# Thermometer1_1.net
KiCad netlist of a schematic drawn in EAGLE
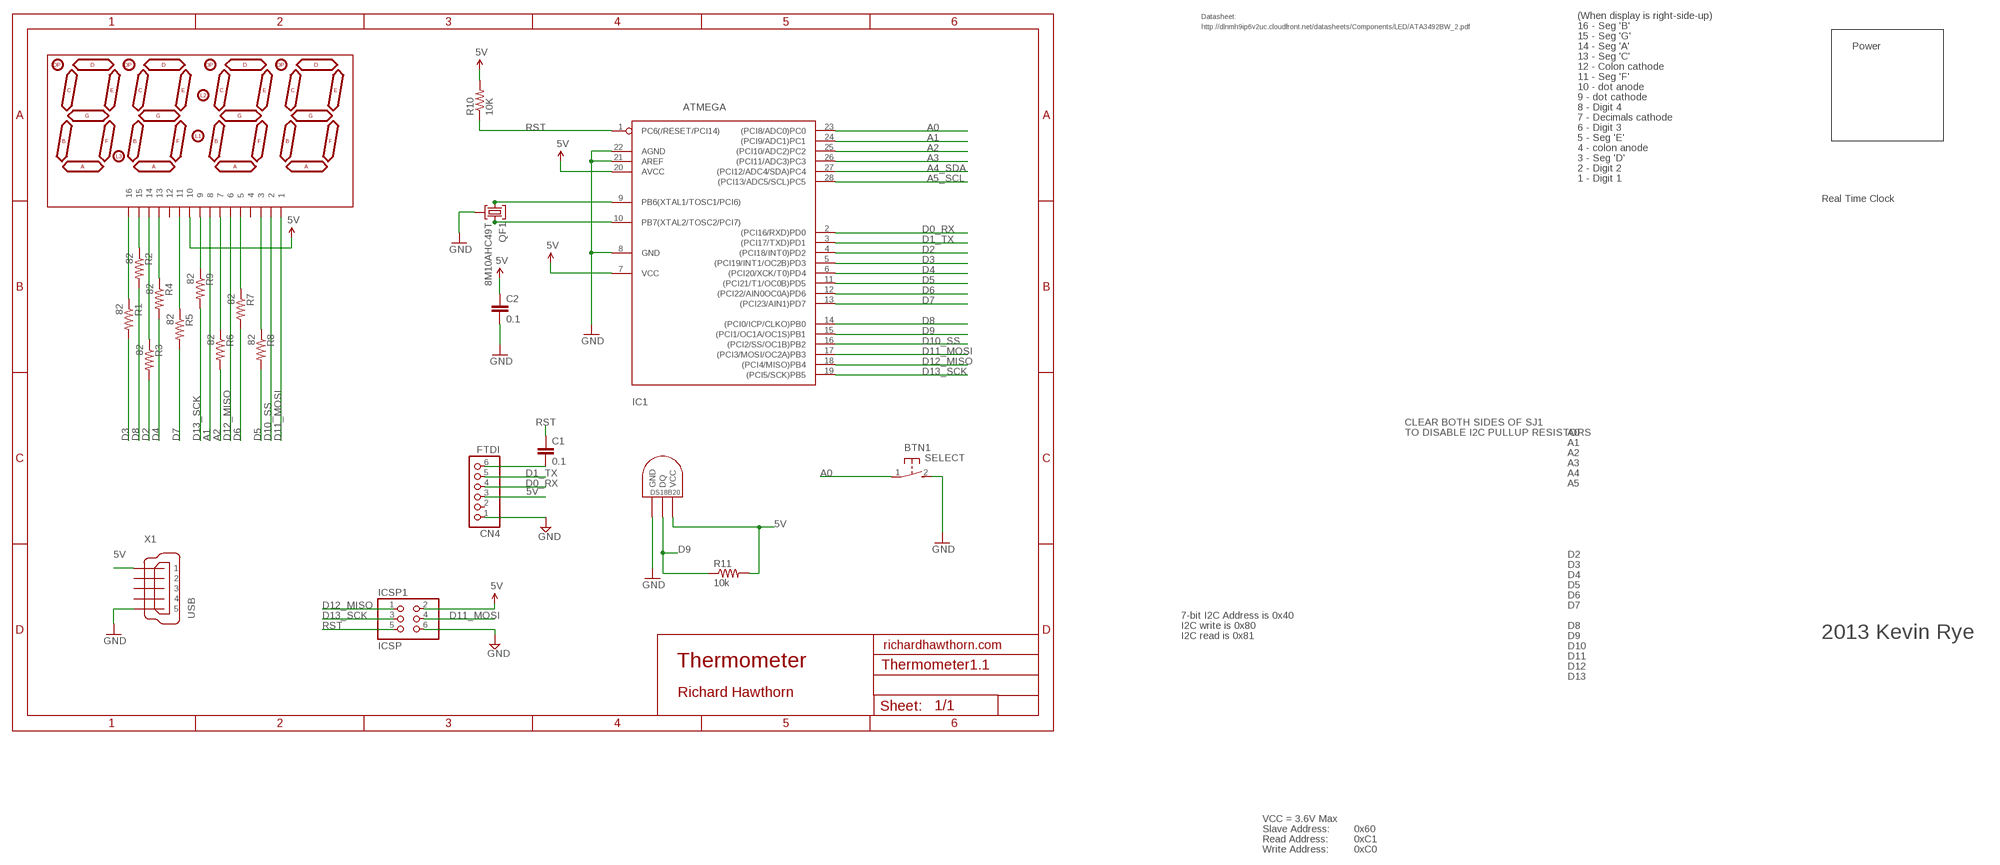
[diagram p0: schematic, sheet 1]

(export (version "E")
  (design (tool "Eeschema 10.0.6"))
  (components
    (comp (ref "BTN1")
      (value "SELECT")
      (footprint "eagle-import:DTS-3")
      (libsource (lib "eagle-import") (part "DTS-3"))
    )
    (comp (ref "C1")
      (value "0.1")
      (footprint "eagle-import:CAP-PTH-SMALL2")
      (libsource (lib "eagle-import") (part "CAPPTH2"))
    )
    (comp (ref "C2")
      (value "0.1")
      (footprint "eagle-import:CAP-PTH-SMALL2")
      (libsource (lib "eagle-import") (part "CAPPTH2"))
    )
    (comp (ref "CN4")
      (value "FTDI")
      (footprint "eagle-import:1X06")
      (libsource (lib "eagle-import") (part "PINHD-1X6"))
    )
    (comp (ref "IC1")
      (value "ATMEGA")
      (footprint "eagle-import:DIL28-3-ROUND")
      (libsource (lib "eagle-import") (part "ATMEGA168PROUND"))
    )
    (comp (ref "ICSP1")
      (value "ICSP")
      (footprint "eagle-import:2X03")
      (libsource (lib "eagle-import") (part "PINHD-2X3"))
    )
    (comp (ref "LED1")
      (value "7SEG-4DIGIT")
      (footprint "eagle-import:SPARKFUN_7-SEGMENT-4DIGIT")
      (libsource (lib "eagle-import") (part "7SEG-4DIGIT"))
    )
    (comp (ref "QF1")
      (value "8M10AHC49T")
      (footprint "eagle-import:HC49U")
      (libsource (lib "eagle-import") (part "8M10AHC49T"))
    )
    (comp (ref "R1")
      (value "82")
      (footprint "eagle-import:0204_7")
      (libsource (lib "eagle-import") (part "R-US_0204/7"))
    )
    (comp (ref "R2")
      (value "82")
      (footprint "eagle-import:0204_7")
      (libsource (lib "eagle-import") (part "R-US_0204/7"))
    )
    (comp (ref "R3")
      (value "82")
      (footprint "eagle-import:0204_7")
      (libsource (lib "eagle-import") (part "R-US_0204/7"))
    )
    (comp (ref "R4")
      (value "82")
      (footprint "eagle-import:0204_7")
      (libsource (lib "eagle-import") (part "R-US_0204/7"))
    )
    (comp (ref "R5")
      (value "82")
      (footprint "eagle-import:0204_7")
      (libsource (lib "eagle-import") (part "R-US_0204/7"))
    )
    (comp (ref "R6")
      (value "82")
      (footprint "eagle-import:0204_7")
      (libsource (lib "eagle-import") (part "R-US_0204/7"))
    )
    (comp (ref "R7")
      (value "82")
      (footprint "eagle-import:0204_7")
      (libsource (lib "eagle-import") (part "R-US_0204/7"))
    )
    (comp (ref "R8")
      (value "82")
      (footprint "eagle-import:0204_7")
      (libsource (lib "eagle-import") (part "R-US_0204/7"))
    )
    (comp (ref "R9")
      (value "82")
      (footprint "eagle-import:0204_7")
      (libsource (lib "eagle-import") (part "R-US_0204/7"))
    )
    (comp (ref "R10")
      (value "10K")
      (footprint "eagle-import:0204_7")
      (libsource (lib "eagle-import") (part "R-US_0204/7"))
    )
    (comp (ref "R11")
      (value "10k")
      (footprint "eagle-import:0204_7")
      (libsource (lib "eagle-import") (part "R-US_0204/7"))
    )
    (comp (ref "U$1")
      (value "DS1820TO92")
      (footprint "eagle-import:DS1820")
      (libsource (lib "eagle-import") (part "DS1820TO92"))
    )
    (comp (ref "X1")
      (value "USB")
      (footprint "eagle-import:32005-601")
      (libsource (lib "eagle-import") (part "MINI-USB_SHIELD5P2-32005-601"))
    )
  )
  (nets
    (net (code "1") (name "/A0") (class "Default")
      (node (ref "BTN1") (pin "1") (pinfunction "1_1") (pintype "passive"))
      (node (ref "IC1") (pin "23") (pinfunction "(PCI8/ADC0)PC0_23") (pintype "bidirectional"))
    )
    (net (code "2") (name "/A1") (class "Default")
      (node (ref "IC1") (pin "24") (pinfunction "(PCI9/ADC1)PC1_24") (pintype "bidirectional"))
      (node (ref "R9") (pin "2") (pinfunction "2_2") (pintype "passive"))
    )
    (net (code "3") (name "/A2") (class "Default")
      (node (ref "IC1") (pin "25") (pinfunction "(PCI10/ADC2)PC2_25") (pintype "bidirectional"))
      (node (ref "R6") (pin "2") (pinfunction "2_2") (pintype "passive"))
    )
    (net (code "4") (name "/A3") (class "Default")
      (node (ref "IC1") (pin "26") (pinfunction "(PCI11/ADC3)PC3_26") (pintype "bidirectional"))
    )
    (net (code "5") (name "/A4_SDA") (class "Default")
      (node (ref "IC1") (pin "27") (pinfunction "(PCI12/ADC4/SDA)PC4_27") (pintype "bidirectional"))
    )
    (net (code "6") (name "/A5_SCL") (class "Default")
      (node (ref "IC1") (pin "28") (pinfunction "(PCI13/ADC5/SCL)PC5_28") (pintype "bidirectional"))
    )
    (net (code "7") (name "/D0_RX") (class "Default")
      (node (ref "CN4") (pin "4") (pinfunction "4_4") (pintype "passive"))
      (node (ref "IC1") (pin "2") (pinfunction "(PCI16/RXD)PD0_2") (pintype "bidirectional"))
    )
    (net (code "8") (name "/D1_TX") (class "Default")
      (node (ref "CN4") (pin "5") (pinfunction "5_5") (pintype "passive"))
      (node (ref "IC1") (pin "3") (pinfunction "(PCI17/TXD)PD1_3") (pintype "bidirectional"))
    )
    (net (code "9") (name "/D2") (class "Default")
      (node (ref "IC1") (pin "4") (pinfunction "(PCI18/INT0)PD2_4") (pintype "bidirectional"))
      (node (ref "R3") (pin "2") (pinfunction "2_2") (pintype "passive"))
    )
    (net (code "10") (name "/D3") (class "Default")
      (node (ref "IC1") (pin "5") (pinfunction "(PCI19/INT1/OC2B)PD3_5") (pintype "bidirectional"))
      (node (ref "R1") (pin "2") (pinfunction "2_2") (pintype "passive"))
    )
    (net (code "11") (name "/D4") (class "Default")
      (node (ref "IC1") (pin "6") (pinfunction "(PCI20/XCK/T0)PD4_6") (pintype "bidirectional"))
      (node (ref "R4") (pin "2") (pinfunction "2_2") (pintype "passive"))
    )
    (net (code "12") (name "/D5") (class "Default")
      (node (ref "IC1") (pin "11") (pinfunction "(PCI21/T1/OC0B)PD5_11") (pintype "bidirectional"))
      (node (ref "R8") (pin "2") (pinfunction "2_2") (pintype "passive"))
    )
    (net (code "13") (name "/D6") (class "Default")
      (node (ref "IC1") (pin "12") (pinfunction "(PCI22/AIN0OC0A)PD6_12") (pintype "bidirectional"))
      (node (ref "R7") (pin "2") (pinfunction "2_2") (pintype "passive"))
    )
    (net (code "14") (name "/D7") (class "Default")
      (node (ref "IC1") (pin "13") (pinfunction "(PCI23/AIN1)PD7_13") (pintype "bidirectional"))
      (node (ref "R5") (pin "2") (pinfunction "2_2") (pintype "passive"))
    )
    (net (code "15") (name "/D8") (class "Default")
      (node (ref "IC1") (pin "14") (pinfunction "(PCI0/ICP/CLKO)PB0_14") (pintype "bidirectional"))
      (node (ref "R2") (pin "2") (pinfunction "2_2") (pintype "passive"))
    )
    (net (code "16") (name "/D9") (class "Default")
      (node (ref "IC1") (pin "15") (pinfunction "(PCI1/OC1A/OC1S)PB1_15") (pintype "bidirectional"))
      (node (ref "R11") (pin "1") (pinfunction "1_1") (pintype "passive"))
      (node (ref "U$1") (pin "DQ") (pinfunction "DQ_DQ") (pintype "bidirectional"))
    )
    (net (code "17") (name "/D10_SS") (class "Default")
      (node (ref "IC1") (pin "16") (pinfunction "(PCI2/SS/OC1B)PB2_16") (pintype "bidirectional"))
      (node (ref "LED1") (pin "1") (pinfunction "1_1") (pintype "bidirectional"))
    )
    (net (code "18") (name "/D11_MOSI") (class "Default")
      (node (ref "IC1") (pin "17") (pinfunction "(PCI3/MOSI/OC2A)PB3_17") (pintype "bidirectional"))
      (node (ref "ICSP1") (pin "4") (pinfunction "4_4") (pintype "passive"))
      (node (ref "LED1") (pin "2") (pinfunction "2_2") (pintype "bidirectional"))
    )
    (net (code "19") (name "/D12_MISO") (class "Default")
      (node (ref "IC1") (pin "18") (pinfunction "(PCI4/MISO)PB4_18") (pintype "bidirectional"))
      (node (ref "ICSP1") (pin "1") (pinfunction "1_1") (pintype "passive"))
      (node (ref "LED1") (pin "6") (pinfunction "6_6") (pintype "bidirectional"))
    )
    (net (code "20") (name "/D13_SCK") (class "Default")
      (node (ref "IC1") (pin "19") (pinfunction "(PCI5/SCK)PB5_19") (pintype "bidirectional"))
      (node (ref "ICSP1") (pin "3") (pinfunction "3_3") (pintype "passive"))
      (node (ref "LED1") (pin "8") (pinfunction "8_8") (pintype "bidirectional"))
    )
    (net (code "21") (name "/RST") (class "Default")
      (node (ref "C1") (pin "1") (pinfunction "1_1") (pintype "passive"))
      (node (ref "IC1") (pin "1") (pinfunction "PC6(/RESET/PCI14)_1") (pintype "bidirectional"))
      (node (ref "ICSP1") (pin "5") (pinfunction "5_5") (pintype "passive"))
      (node (ref "R10") (pin "1") (pinfunction "1_1") (pintype "passive"))
    )
    (net (code "22") (name "5V") (class "Default")
      (node (ref "C2") (pin "1") (pinfunction "1_1") (pintype "passive"))
      (node (ref "CN4") (pin "3") (pinfunction "3_3") (pintype "passive"))
      (node (ref "IC1") (pin "20") (pinfunction "AVCC_20") (pintype "bidirectional"))
      (node (ref "IC1") (pin "7") (pinfunction "VCC_7") (pintype "bidirectional"))
      (node (ref "ICSP1") (pin "2") (pinfunction "2_2") (pintype "passive"))
      (node (ref "LED1") (pin "10") (pinfunction "10_10") (pintype "bidirectional"))
      (node (ref "R10") (pin "2") (pinfunction "2_2") (pintype "passive"))
      (node (ref "R11") (pin "2") (pinfunction "2_2") (pintype "passive"))
      (node (ref "U$1") (pin "VDD") (pinfunction "VCC_VDD") (pintype "power_in"))
      (node (ref "X1") (pin "1") (pinfunction "1_1") (pintype "passive"))
    )
    (net (code "23") (name "GND") (class "Default")
      (node (ref "BTN1") (pin "2") (pinfunction "2_2") (pintype "passive"))
      (node (ref "C2") (pin "2") (pinfunction "2_2") (pintype "passive"))
      (node (ref "CN4") (pin "1") (pinfunction "1_1") (pintype "passive"))
      (node (ref "IC1") (pin "21") (pinfunction "AREF_21") (pintype "bidirectional"))
      (node (ref "IC1") (pin "22") (pinfunction "AGND_22") (pintype "bidirectional"))
      (node (ref "IC1") (pin "8") (pinfunction "GND_8") (pintype "bidirectional"))
      (node (ref "ICSP1") (pin "6") (pinfunction "6_6") (pintype "passive"))
      (node (ref "QF1") (pin "2") (pinfunction "2_2") (pintype "passive"))
      (node (ref "U$1") (pin "GND") (pinfunction "GND_GND") (pintype "power_in"))
      (node (ref "X1") (pin "5") (pinfunction "5_5") (pintype "passive"))
    )
    (net (code "24") (name "Net-(C1-Pad2)") (class "Default")
      (node (ref "C1") (pin "2") (pinfunction "2_2") (pintype "passive"))
      (node (ref "CN4") (pin "6") (pinfunction "6_6") (pintype "passive"))
    )
    (net (code "25") (name "Net-(IC1-PB6(XTAL1{slash}TOSC1{slash}PCI6))") (class "Default")
      (node (ref "IC1") (pin "9") (pinfunction "PB6(XTAL1/TOSC1/PCI6)_9") (pintype "bidirectional"))
      (node (ref "QF1") (pin "1") (pinfunction "1_1") (pintype "passive"))
    )
    (net (code "26") (name "Net-(IC1-PB7(XTAL2{slash}TOSC2{slash}PCI7))") (class "Default")
      (node (ref "IC1") (pin "10") (pinfunction "PB7(XTAL2/TOSC2/PCI7)_10") (pintype "bidirectional"))
      (node (ref "QF1") (pin "3") (pinfunction "3_3") (pintype "passive"))
    )
    (net (code "27") (name "Net-(LED1-Pad3)") (class "Default")
      (node (ref "LED1") (pin "3") (pinfunction "3_3") (pintype "bidirectional"))
      (node (ref "R8") (pin "1") (pinfunction "1_1") (pintype "passive"))
    )
    (net (code "28") (name "Net-(LED1-Pad5)") (class "Default")
      (node (ref "LED1") (pin "5") (pinfunction "5_5") (pintype "bidirectional"))
      (node (ref "R7") (pin "1") (pinfunction "1_1") (pintype "passive"))
    )
    (net (code "29") (name "Net-(LED1-Pad7)") (class "Default")
      (node (ref "LED1") (pin "7") (pinfunction "7_7") (pintype "bidirectional"))
      (node (ref "R6") (pin "1") (pinfunction "1_1") (pintype "passive"))
    )
    (net (code "30") (name "Net-(LED1-Pad9)") (class "Default")
      (node (ref "LED1") (pin "9") (pinfunction "9_9") (pintype "bidirectional"))
      (node (ref "R9") (pin "1") (pinfunction "1_1") (pintype "passive"))
    )
    (net (code "31") (name "Net-(LED1-Pad11)") (class "Default")
      (node (ref "LED1") (pin "11") (pinfunction "11_11") (pintype "bidirectional"))
      (node (ref "R5") (pin "1") (pinfunction "1_1") (pintype "passive"))
    )
    (net (code "32") (name "Net-(LED1-Pad13)") (class "Default")
      (node (ref "LED1") (pin "13") (pinfunction "13_13") (pintype "bidirectional"))
      (node (ref "R4") (pin "1") (pinfunction "1_1") (pintype "passive"))
    )
    (net (code "33") (name "Net-(LED1-Pad14)") (class "Default")
      (node (ref "LED1") (pin "14") (pinfunction "14_14") (pintype "bidirectional"))
      (node (ref "R3") (pin "1") (pinfunction "1_1") (pintype "passive"))
    )
    (net (code "34") (name "Net-(LED1-Pad15)") (class "Default")
      (node (ref "LED1") (pin "15") (pinfunction "15_15") (pintype "bidirectional"))
      (node (ref "R2") (pin "1") (pinfunction "1_1") (pintype "passive"))
    )
    (net (code "35") (name "Net-(LED1-Pad16)") (class "Default")
      (node (ref "LED1") (pin "16") (pinfunction "16_16") (pintype "bidirectional"))
      (node (ref "R1") (pin "1") (pinfunction "1_1") (pintype "passive"))
    )
    (net (code "36") (name "unconnected-(CN4-Pad2)") (class "Default")
      (node (ref "CN4") (pin "2") (pinfunction "2_2") (pintype "passive"))
    )
    (net (code "37") (name "unconnected-(LED1-Pad4)") (class "Default")
      (node (ref "LED1") (pin "4") (pinfunction "4_4") (pintype "bidirectional"))
    )
    (net (code "38") (name "unconnected-(LED1-Pad12)") (class "Default")
      (node (ref "LED1") (pin "12") (pinfunction "12_12") (pintype "bidirectional"))
    )
    (net (code "39") (name "unconnected-(X1-Pad2)") (class "Default")
      (node (ref "X1") (pin "2") (pinfunction "2_2") (pintype "passive"))
    )
    (net (code "40") (name "unconnected-(X1-Pad3)") (class "Default")
      (node (ref "X1") (pin "3") (pinfunction "3_3") (pintype "passive"))
    )
    (net (code "41") (name "unconnected-(X1-Pad4)") (class "Default")
      (node (ref "X1") (pin "4") (pinfunction "4_4") (pintype "passive"))
    )
  )
)
